# top-level.net
KiCad netlist of a schematic drawn in Altium Designer
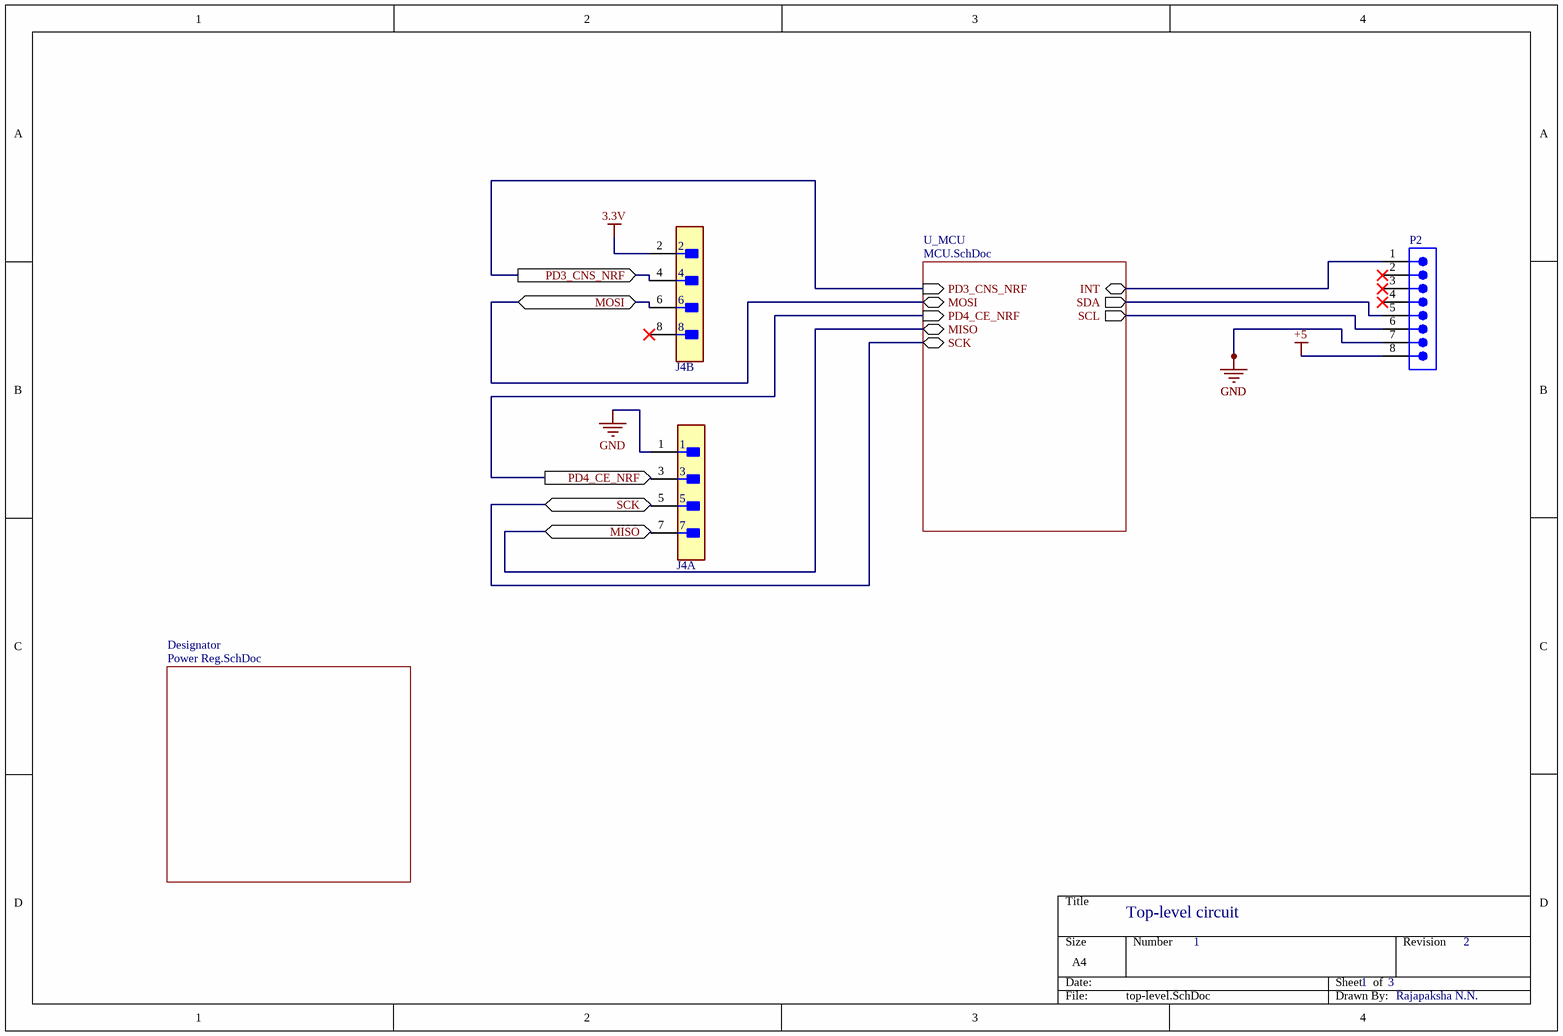
[diagram p0: top-level.SchDoc]

(export (version "E")
  (design (tool "Eeschema 10.0.6"))
  (components
    (comp (ref "J4")
      (value "PBC04DAAN")
      (footprint "FP-PBC04DAAN-MFG")
      (description "CONN HEADER VERT 8POS 2.54MM")
      (libsource (lib "Altium Content Vault") (part "811e954b9c034aa737de4d9295cbe7e"))
    )
    (comp (ref "P2")
      (value "61300811121")
      (footprint "61300811121")
      (libsource (lib "Altium Content Vault") (part "Header_Male_1R_08P"))
    )
  )
  (nets
    (net (code "1") (name "+5") (class "Default")
      (node (ref "P2") (pin "8") (pinfunction "8_8") (pintype "passive"))
    )
    (net (code "3") (name "/INT") (class "Default")
      (node (ref "P2") (pin "1") (pinfunction "1_1") (pintype "passive"))
    )
    (net (code "4") (name "/MISO") (class "Default")
      (node (ref "J4") (pin "7") (pinfunction "7_7") (pintype "passive"))
    )
    (net (code "5") (name "/MOSI") (class "Default")
      (node (ref "J4") (pin "6") (pinfunction "6_6") (pintype "passive"))
    )
    (net (code "6") (name "/PD3_CNS_NRF") (class "Default")
      (node (ref "J4") (pin "4") (pinfunction "4_4") (pintype "passive"))
    )
    (net (code "7") (name "/PD4_CE_NRF") (class "Default")
      (node (ref "J4") (pin "3") (pinfunction "3_3") (pintype "passive"))
    )
    (net (code "8") (name "/SCK") (class "Default")
      (node (ref "J4") (pin "5") (pinfunction "5_5") (pintype "passive"))
    )
    (net (code "9") (name "/SCL") (class "Default")
      (node (ref "P2") (pin "6") (pinfunction "6_6") (pintype "passive"))
    )
    (net (code "10") (name "/SDA") (class "Default")
      (node (ref "P2") (pin "5") (pinfunction "5_5") (pintype "passive"))
    )
    (net (code "11") (name "3.3V") (class "Default")
      (node (ref "J4") (pin "2") (pinfunction "2_2") (pintype "passive"))
    )
    (net (code "12") (name "GND") (class "Default")
      (node (ref "J4") (pin "1") (pinfunction "1_1") (pintype "passive"))
      (node (ref "P2") (pin "7") (pinfunction "7_7") (pintype "passive"))
    )
    (net (code "13") (name "unconnected-(J4-Pad8)") (class "Default")
      (node (ref "J4") (pin "8") (pinfunction "8_8") (pintype "passive+no_connect"))
    )
    (net (code "14") (name "unconnected-(P2-Pad2)") (class "Default")
      (node (ref "P2") (pin "2") (pinfunction "2_2") (pintype "passive+no_connect"))
    )
    (net (code "15") (name "unconnected-(P2-Pad3)") (class "Default")
      (node (ref "P2") (pin "3") (pinfunction "3_3") (pintype "passive+no_connect"))
    )
    (net (code "16") (name "unconnected-(P2-Pad4)") (class "Default")
      (node (ref "P2") (pin "4") (pinfunction "4_4") (pintype "passive+no_connect"))
    )
  )
)
